# Sheet3.net
KiCad netlist of a schematic drawn in Altium Designer
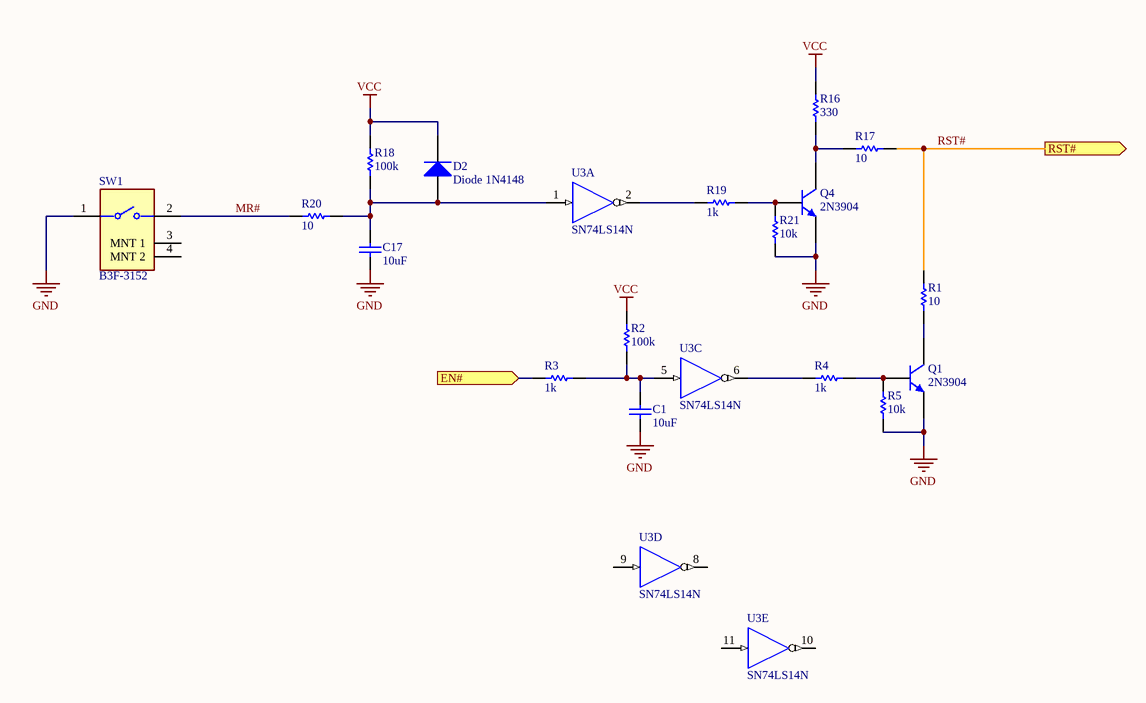
[diagram p0: Sheet3.SchDoc]

(export (version "E")
  (design (tool "Eeschema 10.0.6"))
  (components
    (comp (ref "C1")
      (value "10uF")
      (footprint "RAD-0.3")
      (description "Capacitor")
      (fields (field (name "Comment") "Cap") (field (name "PUBLISHER") "Altium Limited"))
      (libsource (lib "Miscellaneous Devices") (part "Cap"))
    )
    (comp (ref "C17")
      (value "10uF")
      (footprint "RAD-0.3")
      (description "Capacitor")
      (fields (field (name "Comment") "Cap") (field (name "PUBLISHER") "Altium Limited"))
      (libsource (lib "Miscellaneous Devices") (part "Cap"))
    )
    (comp (ref "D2")
      (value "Diode 1N4148")
      (footprint "DO-35")
      (description "High Conductance Fast Diode")
      (fields (field (name "PUBLISHER") "Altium Limited"))
      (libsource (lib "Miscellaneous Devices") (part "Diode 1N4148"))
    )
    (comp (ref "Q1")
      (value "2N3904")
      (footprint "TO-92A")
      (description "NPN General Purpose Amplifier")
      (fields (field (name "PUBLISHER") "Altium Limited"))
      (libsource (lib "Miscellaneous Devices") (part "2N3904"))
    )
    (comp (ref "Q4")
      (value "2N3904")
      (footprint "TO-92A")
      (description "NPN General Purpose Amplifier")
      (fields (field (name "PUBLISHER") "Altium Limited"))
      (libsource (lib "Miscellaneous Devices") (part "2N3904"))
    )
    (comp (ref "R1")
      (value "10")
      (footprint "AXIAL-0.3")
      (description "Resistor")
      (fields (field (name "Comment") "Res1") (field (name "PUBLISHER") "Altium Limited"))
      (libsource (lib "Miscellaneous Devices") (part "Res1"))
    )
    (comp (ref "R2")
      (value "100k")
      (footprint "AXIAL-0.3")
      (description "Resistor")
      (fields (field (name "Comment") "Res1") (field (name "PUBLISHER") "Altium Limited"))
      (libsource (lib "Miscellaneous Devices") (part "Res1"))
    )
    (comp (ref "R3")
      (value "1k")
      (footprint "AXIAL-0.3")
      (description "Resistor")
      (fields (field (name "Comment") "Res1") (field (name "PUBLISHER") "Altium Limited"))
      (libsource (lib "Miscellaneous Devices") (part "Res1"))
    )
    (comp (ref "R4")
      (value "1k")
      (footprint "AXIAL-0.3")
      (description "Resistor")
      (fields (field (name "Comment") "Res1") (field (name "PUBLISHER") "Altium Limited"))
      (libsource (lib "Miscellaneous Devices") (part "Res1"))
    )
    (comp (ref "R5")
      (value "10k")
      (footprint "AXIAL-0.3")
      (description "Resistor")
      (fields (field (name "Comment") "Res1") (field (name "PUBLISHER") "Altium Limited"))
      (libsource (lib "Miscellaneous Devices") (part "Res1"))
    )
    (comp (ref "R16")
      (value "330")
      (footprint "AXIAL-0.3")
      (description "Resistor")
      (fields (field (name "Comment") "Res1") (field (name "PUBLISHER") "Altium Limited"))
      (libsource (lib "Miscellaneous Devices") (part "Res1"))
    )
    (comp (ref "R17")
      (value "10")
      (footprint "AXIAL-0.3")
      (description "Resistor")
      (fields (field (name "Comment") "Res1") (field (name "PUBLISHER") "Altium Limited"))
      (libsource (lib "Miscellaneous Devices") (part "Res1"))
    )
    (comp (ref "R18")
      (value "100k")
      (footprint "AXIAL-0.3")
      (description "Resistor")
      (fields (field (name "Comment") "Res1") (field (name "PUBLISHER") "Altium Limited"))
      (libsource (lib "Miscellaneous Devices") (part "Res1"))
    )
    (comp (ref "R19")
      (value "1k")
      (footprint "AXIAL-0.3")
      (description "Resistor")
      (fields (field (name "Comment") "Res1") (field (name "PUBLISHER") "Altium Limited"))
      (libsource (lib "Miscellaneous Devices") (part "Res1"))
    )
    (comp (ref "R20")
      (value "10")
      (footprint "AXIAL-0.3")
      (description "Resistor")
      (fields (field (name "Comment") "Res1") (field (name "PUBLISHER") "Altium Limited"))
      (libsource (lib "Miscellaneous Devices") (part "Res1"))
    )
    (comp (ref "R21")
      (value "10k")
      (footprint "AXIAL-0.3")
      (description "Resistor")
      (fields (field (name "Comment") "Res1") (field (name "PUBLISHER") "Altium Limited"))
      (libsource (lib "Miscellaneous Devices") (part "Res1"))
    )
    (comp (ref "SW1")
      (value "B3F-3152")
      (footprint "FP-B3F-3152-MFG")
      (description "SWITCH TACTILE SPST-NO 0.05A 24V")
      (libsource (lib "Altium Content Vault") (part "ed2974a2078be5bbdf800c999931250"))
    )
    (comp (ref "U3")
      (value "SN74LS14N")
      (footprint "N014")
      (description "Hex Schmitt-Trigger Inverter")
      (fields (field (name "PUBLISHER") "Altium Limited"))
      (libsource (lib "TI Logic Gate 2") (part "SN74LS14N"))
    )
  )
  (nets
    (net (code "1") (name "/EN#") (class "Default")
      (node (ref "R3") (pin "2") (pinfunction "2_2") (pintype "passive"))
    )
    (net (code "2") (name "/MR#") (class "Default")
      (node (ref "R20") (pin "2") (pinfunction "2_2") (pintype "passive"))
      (node (ref "SW1") (pin "2") (pinfunction "2_2") (pintype "passive"))
    )
    (net (code "3") (name "/RST#") (class "Default")
      (node (ref "R1") (pin "1") (pinfunction "1_1") (pintype "passive"))
      (node (ref "R17") (pin "1") (pinfunction "1_1") (pintype "passive"))
    )
    (net (code "4") (name "GND") (class "Default")
      (node (ref "C1") (pin "1") (pinfunction "1_1") (pintype "passive"))
      (node (ref "C17") (pin "1") (pinfunction "1_1") (pintype "passive"))
      (node (ref "Q1") (pin "1") (pinfunction "E_1") (pintype "passive"))
      (node (ref "Q4") (pin "1") (pinfunction "E_1") (pintype "passive"))
      (node (ref "R21") (pin "2") (pinfunction "2_2") (pintype "passive"))
      (node (ref "R5") (pin "2") (pinfunction "2_2") (pintype "passive"))
      (node (ref "SW1") (pin "1") (pinfunction "1_1") (pintype "passive"))
      (node (ref "U3") (pin "7") (pinfunction "GND_7") (pintype "power_in"))
    )
    (net (code "5") (name "Net-(D2-A)") (class "Default")
      (node (ref "C17") (pin "2") (pinfunction "2_2") (pintype "passive"))
      (node (ref "D2") (pin "1") (pinfunction "A_1") (pintype "passive"))
      (node (ref "R18") (pin "1") (pinfunction "1_1") (pintype "passive"))
      (node (ref "R20") (pin "1") (pinfunction "1_1") (pintype "passive"))
      (node (ref "U3") (pin "1") (pinfunction "A_1") (pintype "input"))
    )
    (net (code "6") (name "Net-(Q1-B)") (class "Default")
      (node (ref "Q1") (pin "2") (pinfunction "B_2") (pintype "passive"))
      (node (ref "R4") (pin "1") (pinfunction "1_1") (pintype "passive"))
      (node (ref "R5") (pin "1") (pinfunction "1_1") (pintype "passive"))
    )
    (net (code "7") (name "Net-(Q1-C)") (class "Default")
      (node (ref "Q1") (pin "3") (pinfunction "C_3") (pintype "passive"))
      (node (ref "R1") (pin "2") (pinfunction "2_2") (pintype "passive"))
    )
    (net (code "8") (name "Net-(Q4-B)") (class "Default")
      (node (ref "Q4") (pin "2") (pinfunction "B_2") (pintype "passive"))
      (node (ref "R19") (pin "1") (pinfunction "1_1") (pintype "passive"))
      (node (ref "R21") (pin "1") (pinfunction "1_1") (pintype "passive"))
    )
    (net (code "9") (name "Net-(Q4-C)") (class "Default")
      (node (ref "Q4") (pin "3") (pinfunction "C_3") (pintype "passive"))
      (node (ref "R16") (pin "2") (pinfunction "2_2") (pintype "passive"))
      (node (ref "R17") (pin "2") (pinfunction "2_2") (pintype "passive"))
    )
    (net (code "10") (name "Net-(U3A-Y)") (class "Default")
      (node (ref "R19") (pin "2") (pinfunction "2_2") (pintype "passive"))
      (node (ref "U3") (pin "2") (pinfunction "Y_2") (pintype "output"))
    )
    (net (code "11") (name "Net-(U3C-A)") (class "Default")
      (node (ref "C1") (pin "2") (pinfunction "2_2") (pintype "passive"))
      (node (ref "R2") (pin "1") (pinfunction "1_1") (pintype "passive"))
      (node (ref "R3") (pin "1") (pinfunction "1_1") (pintype "passive"))
      (node (ref "U3") (pin "5") (pinfunction "A_5") (pintype "input"))
    )
    (net (code "12") (name "Net-(U3C-Y)") (class "Default")
      (node (ref "R4") (pin "2") (pinfunction "2_2") (pintype "passive"))
      (node (ref "U3") (pin "6") (pinfunction "Y_6") (pintype "output"))
    )
    (net (code "13") (name "VCC") (class "Default")
      (node (ref "D2") (pin "2") (pinfunction "K_2") (pintype "passive"))
      (node (ref "R16") (pin "1") (pinfunction "1_1") (pintype "passive"))
      (node (ref "R18") (pin "2") (pinfunction "2_2") (pintype "passive"))
      (node (ref "R2") (pin "2") (pinfunction "2_2") (pintype "passive"))
      (node (ref "U3") (pin "14") (pinfunction "VCC_14") (pintype "power_in"))
    )
    (net (code "14") (name "unconnected-(SW1-MNT_1-Pad3)") (class "Default")
      (node (ref "SW1") (pin "3") (pinfunction "MNT_1_3") (pintype "passive"))
    )
    (net (code "15") (name "unconnected-(SW1-MNT_2-Pad4)") (class "Default")
      (node (ref "SW1") (pin "4") (pinfunction "MNT_2_4") (pintype "passive"))
    )
    (net (code "16") (name "unconnected-(U3D-A-Pad9)") (class "Default")
      (node (ref "U3") (pin "9") (pinfunction "A_9") (pintype "input"))
    )
    (net (code "17") (name "unconnected-(U3D-Y-Pad8)") (class "Default")
      (node (ref "U3") (pin "8") (pinfunction "Y_8") (pintype "output"))
    )
    (net (code "18") (name "unconnected-(U3E-A-Pad11)") (class "Default")
      (node (ref "U3") (pin "11") (pinfunction "A_11") (pintype "input"))
    )
    (net (code "19") (name "unconnected-(U3E-Y-Pad10)") (class "Default")
      (node (ref "U3") (pin "10") (pinfunction "Y_10") (pintype "output"))
    )
  )
)
